# Sensor_Power.net
KiCad netlist of a schematic drawn in Altium Designer
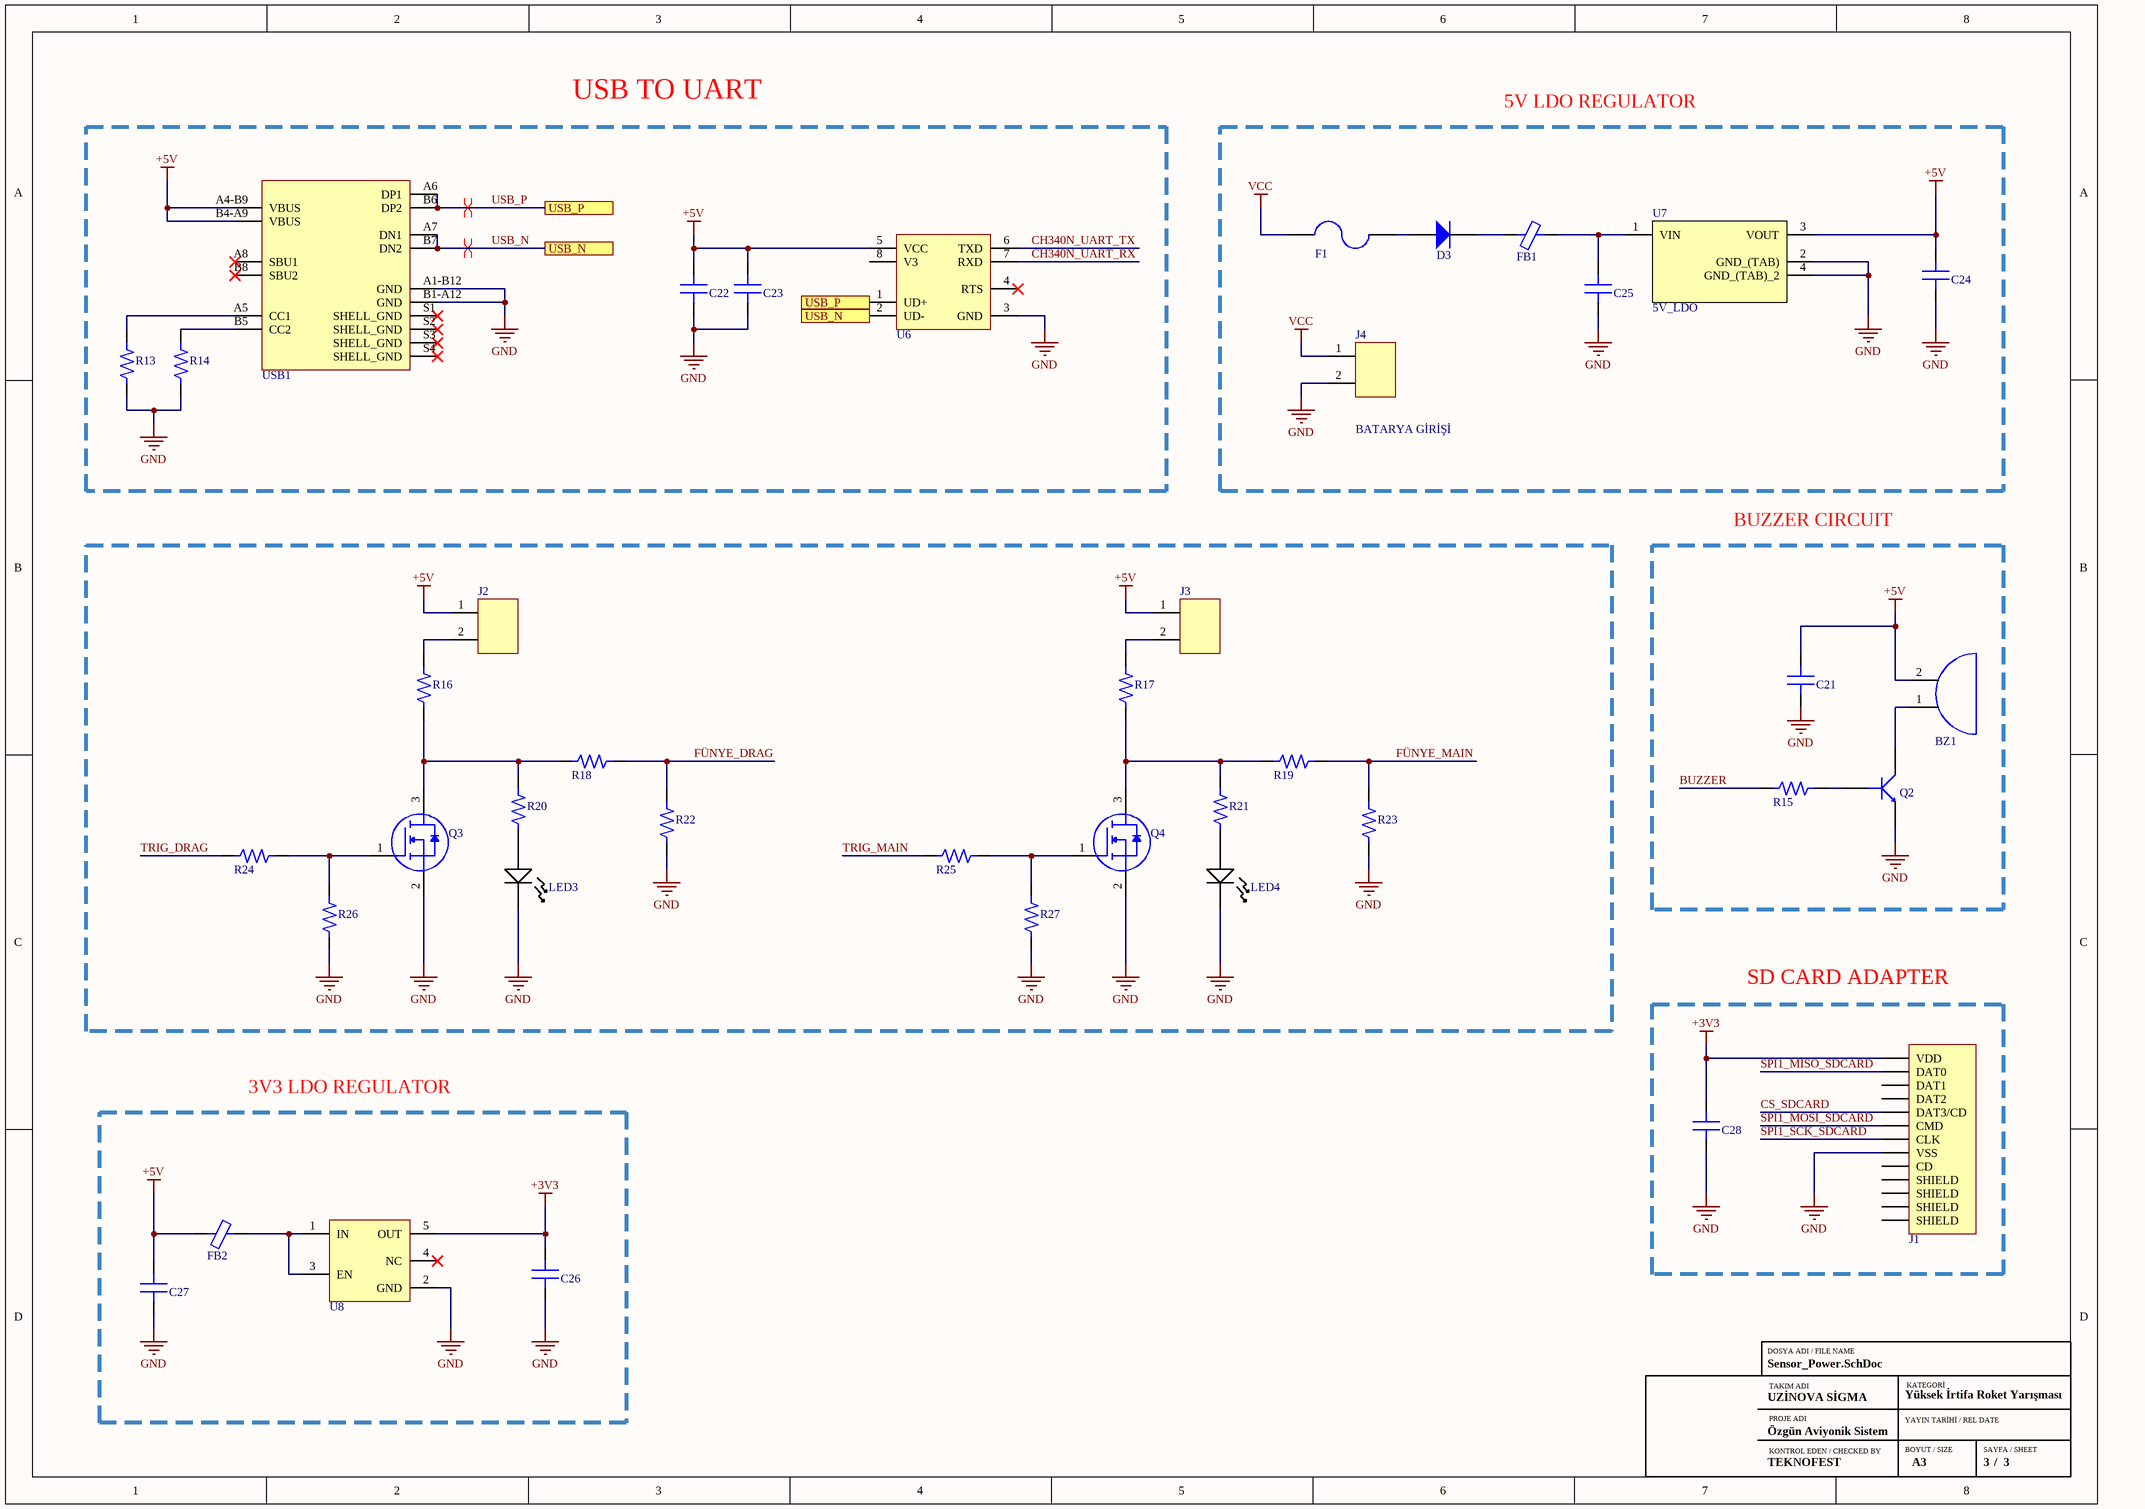
[diagram p0: Sensor_Power.SchDoc]

(export (version "E")
  (design (tool "Eeschema 10.0.6"))
  (components
    (comp (ref "BZ1")
      (value "CMI-9605IC-0580T")
      (footprint "BUZZER")
      (description "Audio Buzzer Magnetic 3VDC 7VDC 30mA 5VDC 85dB 2600Hz to 2800Hz Through Hole Pin Box")
      (fields (field (name "MANUFACTURER") "CUI Devices"))
      (libsource (lib "ROKET_LIBRARY") (part "BUZZER"))
    )
    (comp (ref "C21")
      (value "CAP CER 100nF 0805")
      (footprint "CAP_0805")
      (libsource (lib "ROKET_LIBRARY") (part "CAP CER 100nF 0805"))
    )
    (comp (ref "C22")
      (value "CAP CER 100nF 0805")
      (footprint "CAP_0805")
      (libsource (lib "ROKET_LIBRARY") (part "CAP CER 100nF 0805"))
    )
    (comp (ref "C23")
      (value "CAP CER 100nF 0805")
      (footprint "CAP_0805")
      (libsource (lib "ROKET_LIBRARY") (part "CAP CER 100nF 0805"))
    )
    (comp (ref "C24")
      (value "CAP CER 10uF 0805")
      (footprint "CAP_0805")
      (libsource (lib "ROKET_LIBRARY") (part "CAP CER 10uF 0805"))
    )
    (comp (ref "C25")
      (value "CAP CER 10uF 0805")
      (footprint "CAP_0805")
      (libsource (lib "ROKET_LIBRARY") (part "CAP CER 10uF 0805"))
    )
    (comp (ref "C26")
      (value "CAP CER 1uF 0805")
      (footprint "CAP_0805")
      (libsource (lib "ROKET_LIBRARY") (part "CAP CER 1uF 0805"))
    )
    (comp (ref "C27")
      (value "CAP CER 1uF 0805")
      (footprint "CAP_0805")
      (libsource (lib "ROKET_LIBRARY") (part "CAP CER 1uF 0805"))
    )
    (comp (ref "C28")
      (value "CAP CER 100nF 0805")
      (footprint "CAP_0805")
      (libsource (lib "ROKET_LIBRARY") (part "CAP CER 100nF 0805"))
    )
    (comp (ref "D3")
      (value "DIODE GEN PURP 75V 150MA SOD323F")
      (footprint "SOD323F")
      (description "VR=75V IF=150mA Trr=4ns P=200mW")
      (fields
        (field (name "MANUFACTURER") "ON Semiconductor / Fairchild")
        (field (name "MANUFACTURER PART NUMBER") "1N4148WS")
      )
      (libsource (lib "ROKET_LIBRARY") (part "DIODE"))
    )
    (comp (ref "F1")
      (value "FUSE 3413.0216.22")
      (footprint "FUSE_1206")
      (description "Fuse Chip Fast Acting 1A 32V SMD Solder Pad 1206 Glass T/R VDE/cULus")
      (fields
        (field (name "MANUFACTURER") "Schurter")
        (field (name "MANUFACTURER PART NUMBER") "3413.0216.22")
      )
      (libsource (lib "ROKET_LIBRARY") (part "FUSE"))
    )
    (comp (ref "FB1")
      (value "MPZ2012S601AT000")
      (footprint "FERRITE BEAD_0805")
      (description "0805 600Ω ±25% DCR=0.1Ω 2A")
      (fields (field (name "MANUFACTURER") "TDK"))
      (libsource (lib "ROKET_LIBRARY") (part "FERRITE BEAD"))
    )
    (comp (ref "FB2")
      (value "MPZ2012S601AT000")
      (footprint "FERRITE BEAD_0805")
      (description "0805 600Ω ±25% DCR=0.1Ω 2A")
      (fields (field (name "MANUFACTURER") "TDK"))
      (libsource (lib "ROKET_LIBRARY") (part "FERRITE BEAD"))
    )
    (comp (ref "J1")
      (value "MEM2075-00-140-01-A")
      (footprint "SD CARD")
      (description "MEM2075 Series Normally Open SMT Push-Push MicroSD Memory Card Connector")
      (fields (field (name "MANUFACTURER") "Global Connector Technology"))
      (libsource (lib "ROKET_LIBRARY") (part "SD CARD"))
    )
    (comp (ref "J2")
      (value "Mike Connector")
      (footprint "MIKE CONNECTOR")
      (libsource (lib "ROKET_LIBRARY") (part "Mike Connector"))
    )
    (comp (ref "J3")
      (value "Mike Connector")
      (footprint "MIKE CONNECTOR")
      (libsource (lib "ROKET_LIBRARY") (part "Mike Connector"))
    )
    (comp (ref "J4")
      (value "Mike Connector")
      (footprint "MIKE CONNECTOR")
      (libsource (lib "ROKET_LIBRARY") (part "Mike Connector"))
    )
    (comp (ref "LED3")
      (value "CMD17-21VRD/TR8")
      (footprint "LED RED_0805")
      (description "LED Uni-Color Red 640nm 2-Pin SMT T/R")
      (fields (field (name "MANUFACTURER") "VCC CHML"))
      (libsource (lib "ROKET_LIBRARY") (part "LED RED"))
    )
    (comp (ref "LED4")
      (value "CMD17-21VRD/TR8")
      (footprint "LED RED_0805")
      (description "LED Uni-Color Red 640nm 2-Pin SMT T/R")
      (fields (field (name "MANUFACTURER") "VCC CHML"))
      (libsource (lib "ROKET_LIBRARY") (part "LED RED"))
    )
    (comp (ref "Q2")
      (value "MMBT3904-7-F")
      (footprint "SOT_23F")
      (description "NPN Ic=200mA Vceo=40V hfe=100~300 fT=310MHz P=300mW SOT-23")
      (fields (field (name "MANUFACTURER") "Diodes Zetex"))
      (libsource (lib "ROKET_LIBRARY") (part "BJT_NPN"))
    )
    (comp (ref "Q3")
      (value "NTR5103NT1G")
      (footprint "SOT-23-3")
      (description "MOSFET N-CH 60V 0.26A SOT23")
      (fields (field (name "MANUFACTURER") "ON Semiconductor"))
      (libsource (lib "ROKET_LIBRARY") (part "MOSFET N-Channel"))
    )
    (comp (ref "Q4")
      (value "NTR5103NT1G")
      (footprint "SOT-23-3")
      (description "MOSFET N-CH 60V 0.26A SOT23")
      (fields (field (name "MANUFACTURER") "ON Semiconductor"))
      (libsource (lib "ROKET_LIBRARY") (part "MOSFET N-Channel"))
    )
    (comp (ref "R13")
      (value "RES 10K OHM 0805")
      (footprint "RES_0805")
      (libsource (lib "ROKET_LIBRARY") (part "RES 10K OHM 0805"))
    )
    (comp (ref "R14")
      (value "RES 10K OHM 0805")
      (footprint "RES_0805")
      (libsource (lib "ROKET_LIBRARY") (part "RES 10K OHM 0805"))
    )
    (comp (ref "R15")
      (value "RES 100 OHM 0805")
      (footprint "RES_0805")
      (libsource (lib "ROKET_LIBRARY") (part "RES 100 OHM 0805"))
    )
    (comp (ref "R16")
      (value "RES 0 OHM 0805")
      (footprint "RES_0805")
      (libsource (lib "ROKET_LIBRARY") (part "RES 0 OHM 0805"))
    )
    (comp (ref "R17")
      (value "RES 0 OHM 0805")
      (footprint "RES_0805")
      (libsource (lib "ROKET_LIBRARY") (part "RES 0 OHM 0805"))
    )
    (comp (ref "R18")
      (value "RES 20K OHM 0805")
      (footprint "RES_0805")
      (libsource (lib "ROKET_LIBRARY") (part "RES 20K OHM 0805"))
    )
    (comp (ref "R19")
      (value "RES 20K OHM 0805")
      (footprint "RES_0805")
      (libsource (lib "ROKET_LIBRARY") (part "RES 20K OHM 0805"))
    )
    (comp (ref "R20")
      (value "RES 470 OHM 0805")
      (footprint "RES_0805")
      (libsource (lib "ROKET_LIBRARY") (part "RES 470 OHM 0805"))
    )
    (comp (ref "R21")
      (value "RES 470 OHM 0805")
      (footprint "RES_0805")
      (libsource (lib "ROKET_LIBRARY") (part "RES 470 OHM 0805"))
    )
    (comp (ref "R22")
      (value "RES 10K OHM 0805")
      (footprint "RES_0805")
      (libsource (lib "ROKET_LIBRARY") (part "RES 10K OHM 0805"))
    )
    (comp (ref "R23")
      (value "RES 10K OHM 0805")
      (footprint "RES_0805")
      (libsource (lib "ROKET_LIBRARY") (part "RES 10K OHM 0805"))
    )
    (comp (ref "R24")
      (value "RES 1K OHM 0805")
      (footprint "RES_0805")
      (libsource (lib "ROKET_LIBRARY") (part "RES 1K OHM 0805"))
    )
    (comp (ref "R25")
      (value "RES 1K OHM 0805")
      (footprint "RES_0805")
      (libsource (lib "ROKET_LIBRARY") (part "RES 1K OHM 0805"))
    )
    (comp (ref "R26")
      (value "RES 10K OHM 0805")
      (footprint "RES_0805")
      (libsource (lib "ROKET_LIBRARY") (part "RES 10K OHM 0805"))
    )
    (comp (ref "R27")
      (value "RES 10K OHM 0805")
      (footprint "RES_0805")
      (libsource (lib "ROKET_LIBRARY") (part "RES 10K OHM 0805"))
    )
    (comp (ref "U6")
      (value "CH340N")
      (footprint "SOP-8")
      (description "USB TO UART TTL CONVERTER - SOP 8 PACKAGE")
      (libsource (lib "ROKET_LIBRARY") (part "CH340N"))
    )
    (comp (ref "U7") (value "5V_LDO") (footprint "5V_LDO") (libsource (lib "ROKET_LIBRARY") (part "5V_LDO")))
    (comp (ref "U8")
      (value "NCP161ASN330T1G")
      (footprint "SOT-23-5")
      (description "LDO Regulator, 450 mA, Ultra-High PSRR, Ultra-Low Noise 3.3V, SOT23-5L, Active Discharge")
      (fields (field (name "MANUFACTURER") "ON Semiconductor"))
      (libsource (lib "ROKET_LIBRARY") (part "NCP161ASN330T1G"))
    )
    (comp (ref "USB1")
      (value "USB4125-GF-A")
      (footprint "USB4125-GF-A / Type C USB")
      (description "USB Connector with 1.90mm shell stake length")
      (fields
        (field (name "MANUFACTURER") "Global Connector Technology")
        (field (name "MANUFACTURER PART NUMBER") "USB4125-GF-A-0190")
      )
      (libsource (lib "ROKET_LIBRARY") (part "TYPE C USB CONNECTOR"))
    )
  )
  (nets
    (net (code "1") (name "+3V3") (class "Default")
      (node (ref "C26") (pin "2") (pinfunction "2_2") (pintype "passive"))
      (node (ref "C28") (pin "2") (pinfunction "2_2") (pintype "passive"))
      (node (ref "J1") (pin "P4") (pinfunction "VDD_P4") (pintype "passive"))
      (node (ref "U8") (pin "5") (pinfunction "OUT_5") (pintype "passive"))
    )
    (net (code "2") (name "+5V") (class "Default")
      (node (ref "BZ1") (pin "2") (pinfunction "2_2") (pintype "passive"))
      (node (ref "C21") (pin "2") (pinfunction "2_2") (pintype "passive"))
      (node (ref "C22") (pin "2") (pinfunction "2_2") (pintype "passive"))
      (node (ref "C23") (pin "2") (pinfunction "2_2") (pintype "passive"))
      (node (ref "C24") (pin "2") (pinfunction "2_2") (pintype "passive"))
      (node (ref "C27") (pin "2") (pinfunction "2_2") (pintype "passive"))
      (node (ref "FB2") (pin "1") (pinfunction "1_1") (pintype "passive"))
      (node (ref "J2") (pin "1") (pintype "passive"))
      (node (ref "J3") (pin "1") (pintype "passive"))
      (node (ref "U6") (pin "5") (pinfunction "VCC_5") (pintype "passive"))
      (node (ref "U7") (pin "3") (pinfunction "VOUT_3") (pintype "passive"))
      (node (ref "USB1") (pin "A4-B9") (pinfunction "VBUS_A4-B9") (pintype "passive"))
      (node (ref "USB1") (pin "B4-A9") (pinfunction "VBUS_B4-A9") (pintype "passive"))
    )
    (net (code "3") (name "/BUZZER") (class "Default")
      (node (ref "R15") (pin "1") (pinfunction "1_1") (pintype "passive"))
    )
    (net (code "4") (name "/CH340N_UART_RX") (class "Default")
      (node (ref "U6") (pin "7") (pinfunction "RXD_7") (pintype "passive"))
    )
    (net (code "5") (name "/CH340N_UART_TX") (class "Default")
      (node (ref "U6") (pin "6") (pinfunction "TXD_6") (pintype "passive"))
    )
    (net (code "6") (name "/CS_SDCARD") (class "Default")
      (node (ref "J1") (pin "P2") (pinfunction "DAT3/CD_P2") (pintype "passive"))
    )
    (net (code "7") (name "/FÜNYE_DRAG") (class "Default")
      (node (ref "R18") (pin "2") (pinfunction "2_2") (pintype "passive"))
      (node (ref "R22") (pin "2") (pinfunction "2_2") (pintype "passive"))
    )
    (net (code "8") (name "/FÜNYE_MAIN") (class "Default")
      (node (ref "R19") (pin "2") (pinfunction "2_2") (pintype "passive"))
      (node (ref "R23") (pin "2") (pinfunction "2_2") (pintype "passive"))
    )
    (net (code "9") (name "/SPI1_MISO_SDCARD") (class "Default")
      (node (ref "J1") (pin "P7") (pinfunction "DAT0_P7") (pintype "passive"))
    )
    (net (code "10") (name "/SPI1_MOSI_SDCARD") (class "Default")
      (node (ref "J1") (pin "P3") (pinfunction "CMD_P3") (pintype "passive"))
    )
    (net (code "11") (name "/SPI1_SCK_SDCARD") (class "Default")
      (node (ref "J1") (pin "P5") (pinfunction "CLK_P5") (pintype "passive"))
    )
    (net (code "12") (name "/TRIG_DRAG") (class "Default")
      (node (ref "R24") (pin "1") (pinfunction "1_1") (pintype "passive"))
    )
    (net (code "13") (name "/TRIG_MAIN") (class "Default")
      (node (ref "R25") (pin "1") (pinfunction "1_1") (pintype "passive"))
    )
    (net (code "14") (name "/USB_N") (class "Default")
      (node (ref "U6") (pin "2") (pinfunction "UD-_2") (pintype "passive"))
      (node (ref "USB1") (pin "A7") (pinfunction "DN1_A7") (pintype "passive"))
      (node (ref "USB1") (pin "B7") (pinfunction "DN2_B7") (pintype "passive"))
    )
    (net (code "15") (name "/USB_P") (class "Default")
      (node (ref "U6") (pin "1") (pinfunction "UD+_1") (pintype "passive"))
      (node (ref "USB1") (pin "A6") (pinfunction "DP1_A6") (pintype "passive"))
      (node (ref "USB1") (pin "B6") (pinfunction "DP2_B6") (pintype "passive"))
    )
    (net (code "16") (name "GND") (class "Default")
      (node (ref "C21") (pin "1") (pinfunction "1_1") (pintype "passive"))
      (node (ref "C22") (pin "1") (pinfunction "1_1") (pintype "passive"))
      (node (ref "C23") (pin "1") (pinfunction "1_1") (pintype "passive"))
      (node (ref "C24") (pin "1") (pinfunction "1_1") (pintype "passive"))
      (node (ref "C25") (pin "1") (pinfunction "1_1") (pintype "passive"))
      (node (ref "C26") (pin "1") (pinfunction "1_1") (pintype "passive"))
      (node (ref "C27") (pin "1") (pinfunction "1_1") (pintype "passive"))
      (node (ref "C28") (pin "1") (pinfunction "1_1") (pintype "passive"))
      (node (ref "J1") (pin "P6") (pinfunction "VSS_P6") (pintype "passive"))
      (node (ref "J4") (pin "2") (pintype "passive"))
      (node (ref "LED3") (pin "2") (pinfunction "2_2") (pintype "passive"))
      (node (ref "LED4") (pin "2") (pinfunction "2_2") (pintype "passive"))
      (node (ref "Q2") (pin "2") (pinfunction "E_2") (pintype "passive"))
      (node (ref "Q3") (pin "2") (pinfunction "S_2") (pintype "passive"))
      (node (ref "Q4") (pin "2") (pinfunction "S_2") (pintype "passive"))
      (node (ref "R13") (pin "1") (pinfunction "1_1") (pintype "passive"))
      (node (ref "R14") (pin "1") (pinfunction "1_1") (pintype "passive"))
      (node (ref "R22") (pin "1") (pinfunction "1_1") (pintype "passive"))
      (node (ref "R23") (pin "1") (pinfunction "1_1") (pintype "passive"))
      (node (ref "R26") (pin "1") (pinfunction "1_1") (pintype "passive"))
      (node (ref "R27") (pin "1") (pinfunction "1_1") (pintype "passive"))
      (node (ref "U6") (pin "3") (pinfunction "GND_3") (pintype "passive"))
      (node (ref "U7") (pin "2") (pinfunction "GND_(TAB)_2") (pintype "passive"))
      (node (ref "U7") (pin "4") (pinfunction "GND_(TAB)_2_4") (pintype "passive"))
      (node (ref "U8") (pin "2") (pinfunction "GND_2") (pintype "passive"))
      (node (ref "USB1") (pin "A1-B12") (pinfunction "GND_A1-B12") (pintype "passive"))
      (node (ref "USB1") (pin "B1-A12") (pinfunction "GND_B1-A12") (pintype "passive"))
    )
    (net (code "17") (name "Net-(D3-ANODE)") (class "Default")
      (node (ref "D3") (pin "2") (pinfunction "ANODE_2") (pintype "passive"))
      (node (ref "F1") (pin "2") (pinfunction "2_2") (pintype "passive"))
    )
    (net (code "18") (name "Net-(D3-CATHODE)") (class "Default")
      (node (ref "D3") (pin "1") (pinfunction "CATHODE_1") (pintype "passive"))
      (node (ref "FB1") (pin "1") (pinfunction "1_1") (pintype "passive"))
    )
    (net (code "19") (name "Net-(J2-Pad2)") (class "Default")
      (node (ref "J2") (pin "2") (pintype "passive"))
      (node (ref "R16") (pin "2") (pinfunction "2_2") (pintype "passive"))
    )
    (net (code "20") (name "Net-(J3-Pad2)") (class "Default")
      (node (ref "J3") (pin "2") (pintype "passive"))
      (node (ref "R17") (pin "2") (pinfunction "2_2") (pintype "passive"))
    )
    (net (code "21") (name "Net-(LED3-Pad1)") (class "Default")
      (node (ref "LED3") (pin "1") (pinfunction "1_1") (pintype "passive"))
      (node (ref "R20") (pin "1") (pinfunction "1_1") (pintype "passive"))
    )
    (net (code "22") (name "Net-(LED4-Pad1)") (class "Default")
      (node (ref "LED4") (pin "1") (pinfunction "1_1") (pintype "passive"))
      (node (ref "R21") (pin "1") (pinfunction "1_1") (pintype "passive"))
    )
    (net (code "23") (name "Net-(Q2-B)") (class "Default")
      (node (ref "Q2") (pin "1") (pinfunction "B_1") (pintype "passive"))
      (node (ref "R15") (pin "2") (pinfunction "2_2") (pintype "passive"))
    )
    (net (code "24") (name "Net-(Q2-C)") (class "Default")
      (node (ref "BZ1") (pin "1") (pinfunction "1_1") (pintype "passive"))
      (node (ref "Q2") (pin "3") (pinfunction "C_3") (pintype "passive"))
    )
    (net (code "25") (name "Net-(Q3-D)") (class "Default")
      (node (ref "Q3") (pin "3") (pinfunction "D_3") (pintype "passive"))
      (node (ref "R16") (pin "1") (pinfunction "1_1") (pintype "passive"))
      (node (ref "R18") (pin "1") (pinfunction "1_1") (pintype "passive"))
      (node (ref "R20") (pin "2") (pinfunction "2_2") (pintype "passive"))
    )
    (net (code "26") (name "Net-(Q3-G)") (class "Default")
      (node (ref "Q3") (pin "1") (pinfunction "G_1") (pintype "passive"))
      (node (ref "R24") (pin "2") (pinfunction "2_2") (pintype "passive"))
      (node (ref "R26") (pin "2") (pinfunction "2_2") (pintype "passive"))
    )
    (net (code "27") (name "Net-(Q4-D)") (class "Default")
      (node (ref "Q4") (pin "3") (pinfunction "D_3") (pintype "passive"))
      (node (ref "R17") (pin "1") (pinfunction "1_1") (pintype "passive"))
      (node (ref "R19") (pin "1") (pinfunction "1_1") (pintype "passive"))
      (node (ref "R21") (pin "2") (pinfunction "2_2") (pintype "passive"))
    )
    (net (code "28") (name "Net-(Q4-G)") (class "Default")
      (node (ref "Q4") (pin "1") (pinfunction "G_1") (pintype "passive"))
      (node (ref "R25") (pin "2") (pinfunction "2_2") (pintype "passive"))
      (node (ref "R27") (pin "2") (pinfunction "2_2") (pintype "passive"))
    )
    (net (code "29") (name "Net-(U7-VIN)") (class "Default")
      (node (ref "C25") (pin "2") (pinfunction "2_2") (pintype "passive"))
      (node (ref "FB1") (pin "2") (pinfunction "2_2") (pintype "passive"))
      (node (ref "U7") (pin "1") (pinfunction "VIN_1") (pintype "passive"))
    )
    (net (code "30") (name "Net-(U8-EN)") (class "Default")
      (node (ref "FB2") (pin "2") (pinfunction "2_2") (pintype "passive"))
      (node (ref "U8") (pin "1") (pinfunction "IN_1") (pintype "passive"))
      (node (ref "U8") (pin "3") (pinfunction "EN_3") (pintype "passive"))
    )
    (net (code "31") (name "Net-(USB1-CC1)") (class "Default")
      (node (ref "R13") (pin "2") (pinfunction "2_2") (pintype "passive"))
      (node (ref "USB1") (pin "A5") (pinfunction "CC1_A5") (pintype "passive"))
    )
    (net (code "32") (name "Net-(USB1-CC2)") (class "Default")
      (node (ref "R14") (pin "2") (pinfunction "2_2") (pintype "passive"))
      (node (ref "USB1") (pin "B5") (pinfunction "CC2_B5") (pintype "passive"))
    )
    (net (code "33") (name "VCC") (class "Default")
      (node (ref "F1") (pin "1") (pinfunction "1_1") (pintype "passive"))
      (node (ref "J4") (pin "1") (pintype "passive"))
    )
    (net (code "34") (name "unconnected-(J1-CD-PadP9)") (class "Default")
      (node (ref "J1") (pin "P9") (pinfunction "CD_P9") (pintype "passive"))
    )
    (net (code "35") (name "unconnected-(J1-DAT1-PadP8)") (class "Default")
      (node (ref "J1") (pin "P8") (pinfunction "DAT1_P8") (pintype "passive"))
    )
    (net (code "36") (name "unconnected-(J1-DAT2-PadP1)") (class "Default")
      (node (ref "J1") (pin "P1") (pinfunction "DAT2_P1") (pintype "passive"))
    )
    (net (code "37") (name "unconnected-(J1-SHIELD-PadSH1)") (class "Default")
      (node (ref "J1") (pin "SH1") (pinfunction "SHIELD_SH1") (pintype "passive"))
    )
    (net (code "38") (name "unconnected-(J1-SHIELD-PadSH2)") (class "Default")
      (node (ref "J1") (pin "SH2") (pinfunction "SHIELD_SH2") (pintype "passive"))
    )
    (net (code "39") (name "unconnected-(J1-SHIELD-PadSH3)") (class "Default")
      (node (ref "J1") (pin "SH3") (pinfunction "SHIELD_SH3") (pintype "passive"))
    )
    (net (code "40") (name "unconnected-(J1-SHIELD-PadSH4)") (class "Default")
      (node (ref "J1") (pin "SH4") (pinfunction "SHIELD_SH4") (pintype "passive"))
    )
    (net (code "41") (name "unconnected-(U6-RTS-Pad4)") (class "Default")
      (node (ref "U6") (pin "4") (pinfunction "RTS_4") (pintype "passive+no_connect"))
    )
    (net (code "42") (name "unconnected-(U6-V3-Pad8)") (class "Default")
      (node (ref "U6") (pin "8") (pinfunction "V3_8") (pintype "passive"))
    )
    (net (code "43") (name "unconnected-(U8-NC-Pad4)") (class "Default")
      (node (ref "U8") (pin "4") (pinfunction "NC_4") (pintype "passive+no_connect"))
    )
    (net (code "44") (name "unconnected-(USB1-SBU1-PadA8)") (class "Default")
      (node (ref "USB1") (pin "A8") (pinfunction "SBU1_A8") (pintype "passive+no_connect"))
    )
    (net (code "45") (name "unconnected-(USB1-SBU2-PadB8)") (class "Default")
      (node (ref "USB1") (pin "B8") (pinfunction "SBU2_B8") (pintype "passive+no_connect"))
    )
    (net (code "46") (name "unconnected-(USB1-SHELL_GND-PadS1)") (class "Default")
      (node (ref "USB1") (pin "S1") (pinfunction "SHELL_GND_S1") (pintype "passive+no_connect"))
    )
    (net (code "47") (name "unconnected-(USB1-SHELL_GND-PadS2)") (class "Default")
      (node (ref "USB1") (pin "S2") (pinfunction "SHELL_GND_S2") (pintype "passive+no_connect"))
    )
    (net (code "48") (name "unconnected-(USB1-SHELL_GND-PadS3)") (class "Default")
      (node (ref "USB1") (pin "S3") (pinfunction "SHELL_GND_S3") (pintype "passive+no_connect"))
    )
    (net (code "49") (name "unconnected-(USB1-SHELL_GND-PadS4)") (class "Default")
      (node (ref "USB1") (pin "S4") (pinfunction "SHELL_GND_S4") (pintype "passive+no_connect"))
    )
  )
)
